# biggity.net
KiCad netlist of a schematic drawn in EAGLE
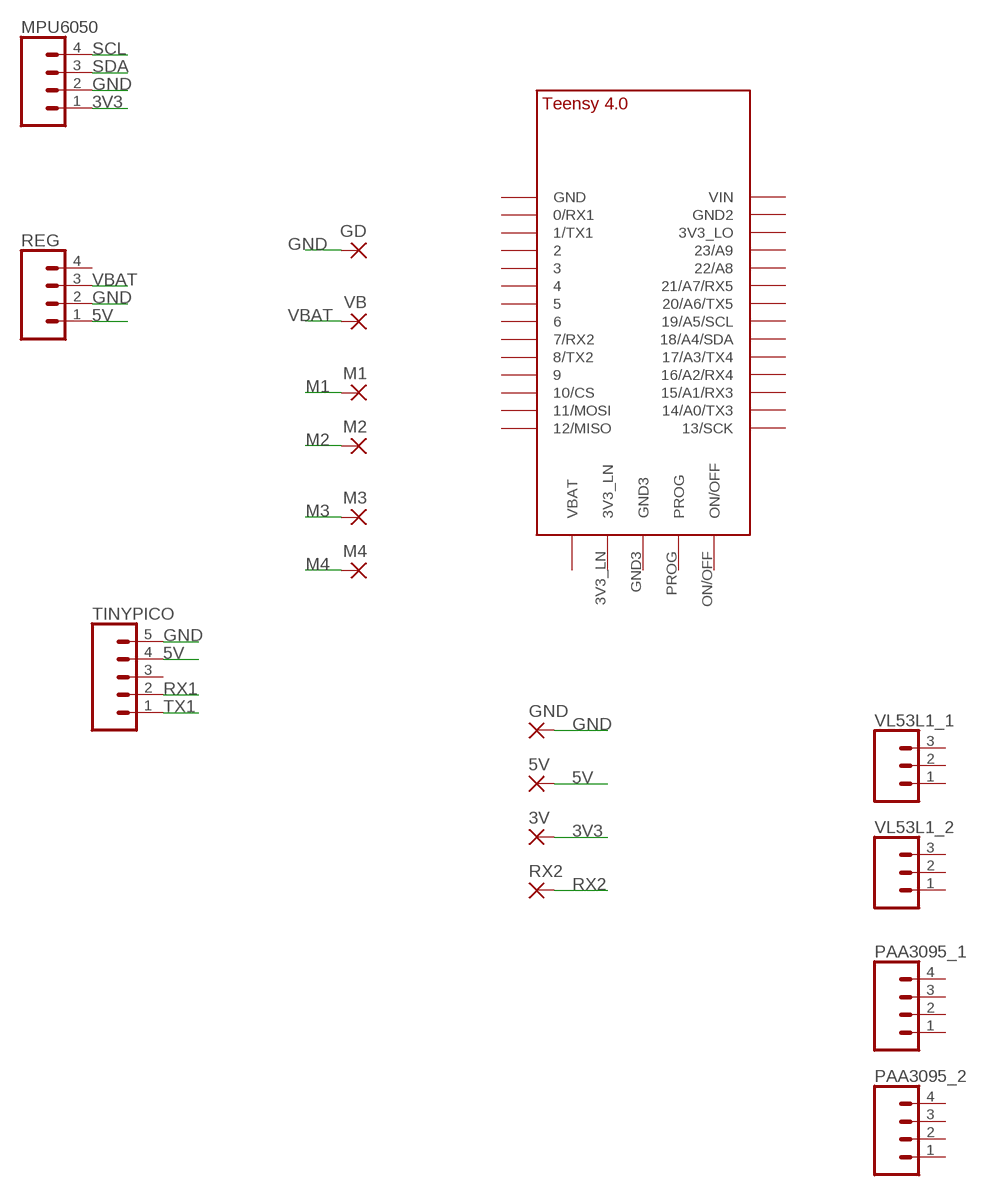
[diagram p0: schematic, sheet 1]

(export (version "E")
  (design (tool "Eeschema 10.0.6"))
  (components
    (comp (ref "3V")
      (value "SMD2")
      (footprint "eagle-import:SMD1,27-2,54")
      (libsource (lib "eagle-import") (part "SMD2"))
    )
    (comp (ref "5V")
      (value "SMD2")
      (footprint "eagle-import:SMD1,27-2,54")
      (libsource (lib "eagle-import") (part "SMD2"))
    )
    (comp (ref "GD")
      (value "SMD2")
      (footprint "eagle-import:SMD1,27-2,54")
      (libsource (lib "eagle-import") (part "SMD2"))
    )
    (comp (ref "GND")
      (value "SMD2")
      (footprint "eagle-import:SMD1,27-2,54")
      (libsource (lib "eagle-import") (part "SMD2"))
    )
    (comp (ref "M1")
      (value "SMD2")
      (footprint "eagle-import:SMD1,27-2,54")
      (libsource (lib "eagle-import") (part "SMD2"))
    )
    (comp (ref "M2")
      (value "SMD2")
      (footprint "eagle-import:SMD1,27-2,54")
      (libsource (lib "eagle-import") (part "SMD2"))
    )
    (comp (ref "M3")
      (value "SMD2")
      (footprint "eagle-import:SMD1,27-2,54")
      (libsource (lib "eagle-import") (part "SMD2"))
    )
    (comp (ref "M4")
      (value "SMD2")
      (footprint "eagle-import:SMD1,27-2,54")
      (libsource (lib "eagle-import") (part "SMD2"))
    )
    (comp (ref "MPU6050")
      (value "CONN_041X04_NO_SILK")
      (footprint "eagle-import:1X04_NO_SILK")
      (libsource (lib "eagle-import") (part "CONN_041X04_NO_SILK"))
    )
    (comp (ref "PAA3095_1")
      (value "CONN_041X04_NO_SILK")
      (footprint "eagle-import:1X04_NO_SILK")
      (libsource (lib "eagle-import") (part "CONN_041X04_NO_SILK"))
    )
    (comp (ref "PAA3095_2")
      (value "CONN_041X04_NO_SILK")
      (footprint "eagle-import:1X04_NO_SILK")
      (libsource (lib "eagle-import") (part "CONN_041X04_NO_SILK"))
    )
    (comp (ref "REG")
      (value "CONN_041X04_NO_SILK")
      (footprint "eagle-import:1X04_NO_SILK")
      (libsource (lib "eagle-import") (part "CONN_041X04_NO_SILK"))
    )
    (comp (ref "RX2")
      (value "SMD2")
      (footprint "eagle-import:SMD1,27-2,54")
      (libsource (lib "eagle-import") (part "SMD2"))
    )
    (comp (ref "TINYPICO")
      (value "CONN_05NO_SILK")
      (footprint "eagle-import:1X05_NO_SILK")
      (libsource (lib "eagle-import") (part "CONN_05NO_SILK"))
    )
    (comp (ref "U$1")
      (value "TEENSY_4.0")
      (footprint "eagle-import:TEENSY_4.0")
      (libsource (lib "eagle-import") (part "TEENSY_4.0"))
    )
    (comp (ref "VB")
      (value "SMD2")
      (footprint "eagle-import:SMD1,27-2,54")
      (libsource (lib "eagle-import") (part "SMD2"))
    )
    (comp (ref "VL53L1_1")
      (value "CONN_031X03_NO_SILK")
      (footprint "eagle-import:1X03_NO_SILK")
      (libsource (lib "eagle-import") (part "CONN_031X03_NO_SILK"))
    )
    (comp (ref "VL53L1_2")
      (value "CONN_031X03_NO_SILK")
      (footprint "eagle-import:1X03_NO_SILK")
      (libsource (lib "eagle-import") (part "CONN_031X03_NO_SILK"))
    )
  )
  (nets
    (net (code "1") (name "/3V3") (class "Default")
      (node (ref "3V") (pin "1") (pinfunction "P_1") (pintype "passive"))
      (node (ref "MPU6050") (pin "1") (pinfunction "1_1") (pintype "passive"))
    )
    (net (code "2") (name "/5V") (class "Default")
      (node (ref "5V") (pin "1") (pinfunction "P_1") (pintype "passive"))
      (node (ref "REG") (pin "1") (pinfunction "1_1") (pintype "passive"))
      (node (ref "TINYPICO") (pin "4") (pinfunction "4_4") (pintype "passive"))
    )
    (net (code "3") (name "/GND") (class "Default")
      (node (ref "GD") (pin "1") (pinfunction "P_1") (pintype "passive"))
      (node (ref "GND") (pin "1") (pinfunction "P_1") (pintype "passive"))
      (node (ref "MPU6050") (pin "2") (pinfunction "2_2") (pintype "passive"))
      (node (ref "REG") (pin "2") (pinfunction "2_2") (pintype "passive"))
      (node (ref "TINYPICO") (pin "5") (pinfunction "5_5") (pintype "passive"))
    )
    (net (code "4") (name "/M1") (class "Default")
      (node (ref "M1") (pin "1") (pinfunction "P_1") (pintype "passive"))
    )
    (net (code "5") (name "/M2") (class "Default")
      (node (ref "M2") (pin "1") (pinfunction "P_1") (pintype "passive"))
    )
    (net (code "6") (name "/M3") (class "Default")
      (node (ref "M3") (pin "1") (pinfunction "P_1") (pintype "passive"))
    )
    (net (code "7") (name "/M4") (class "Default")
      (node (ref "M4") (pin "1") (pinfunction "P_1") (pintype "passive"))
    )
    (net (code "8") (name "/RX1") (class "Default")
      (node (ref "TINYPICO") (pin "2") (pinfunction "2_2") (pintype "passive"))
    )
    (net (code "9") (name "/RX2") (class "Default")
      (node (ref "RX2") (pin "1") (pinfunction "P_1") (pintype "passive"))
    )
    (net (code "10") (name "/SCL") (class "Default")
      (node (ref "MPU6050") (pin "4") (pinfunction "4_4") (pintype "passive"))
    )
    (net (code "11") (name "/SDA") (class "Default")
      (node (ref "MPU6050") (pin "3") (pinfunction "3_3") (pintype "passive"))
    )
    (net (code "12") (name "/TX1") (class "Default")
      (node (ref "TINYPICO") (pin "1") (pinfunction "1_1") (pintype "passive"))
    )
    (net (code "13") (name "/VBAT") (class "Default")
      (node (ref "REG") (pin "3") (pinfunction "3_3") (pintype "passive"))
      (node (ref "VB") (pin "1") (pinfunction "P_1") (pintype "passive"))
    )
    (net (code "14") (name "unconnected-(PAA3095_1-Pad1)") (class "Default")
      (node (ref "PAA3095_1") (pin "1") (pinfunction "1_1") (pintype "passive"))
    )
    (net (code "15") (name "unconnected-(PAA3095_1-Pad2)") (class "Default")
      (node (ref "PAA3095_1") (pin "2") (pinfunction "2_2") (pintype "passive"))
    )
    (net (code "16") (name "unconnected-(PAA3095_1-Pad3)") (class "Default")
      (node (ref "PAA3095_1") (pin "3") (pinfunction "3_3") (pintype "passive"))
    )
    (net (code "17") (name "unconnected-(PAA3095_1-Pad4)") (class "Default")
      (node (ref "PAA3095_1") (pin "4") (pinfunction "4_4") (pintype "passive"))
    )
    (net (code "18") (name "unconnected-(PAA3095_2-Pad1)") (class "Default")
      (node (ref "PAA3095_2") (pin "1") (pinfunction "1_1") (pintype "passive"))
    )
    (net (code "19") (name "unconnected-(PAA3095_2-Pad2)") (class "Default")
      (node (ref "PAA3095_2") (pin "2") (pinfunction "2_2") (pintype "passive"))
    )
    (net (code "20") (name "unconnected-(PAA3095_2-Pad3)") (class "Default")
      (node (ref "PAA3095_2") (pin "3") (pinfunction "3_3") (pintype "passive"))
    )
    (net (code "21") (name "unconnected-(PAA3095_2-Pad4)") (class "Default")
      (node (ref "PAA3095_2") (pin "4") (pinfunction "4_4") (pintype "passive"))
    )
    (net (code "22") (name "unconnected-(REG-Pad4)") (class "Default")
      (node (ref "REG") (pin "4") (pinfunction "4_4") (pintype "passive"))
    )
    (net (code "23") (name "unconnected-(TINYPICO-Pad3)") (class "Default")
      (node (ref "TINYPICO") (pin "3") (pinfunction "3_3") (pintype "passive"))
    )
    (net (code "24") (name "unconnected-(U$1-0{slash}RX1-Pad0{slash}RX)") (class "Default")
      (node (ref "U$1") (pin "0/RX") (pinfunction "0/RX1_0/RX") (pintype "bidirectional"))
    )
    (net (code "25") (name "unconnected-(U$1-1{slash}TX1-Pad1{slash}TX)") (class "Default")
      (node (ref "U$1") (pin "1/TX") (pinfunction "1/TX1_1/TX") (pintype "bidirectional"))
    )
    (net (code "26") (name "unconnected-(U$1-3-Pad3{slash}CANTX)") (class "Default")
      (node (ref "U$1") (pin "3/CANTX") (pinfunction "3_3/CANTX") (pintype "bidirectional"))
    )
    (net (code "27") (name "unconnected-(U$1-4-Pad4{slash}CANRX)") (class "Default")
      (node (ref "U$1") (pin "4/CANRX") (pinfunction "4_4/CANRX") (pintype "bidirectional"))
    )
    (net (code "28") (name "unconnected-(U$1-7{slash}RX2-Pad7)") (class "Default")
      (node (ref "U$1") (pin "7") (pinfunction "7/RX2_7") (pintype "bidirectional"))
    )
    (net (code "29") (name "unconnected-(U$1-8{slash}TX2-Pad8)") (class "Default")
      (node (ref "U$1") (pin "8") (pinfunction "8/TX2_8") (pintype "bidirectional"))
    )
    (net (code "30") (name "unconnected-(U$1-9-Pad9{slash}CS)") (class "Default")
      (node (ref "U$1") (pin "9/CS") (pinfunction "9_9/CS") (pintype "bidirectional"))
    )
    (net (code "31") (name "unconnected-(U$1-14{slash}A0{slash}TX3-Pad14{slash}A0)") (class "Default")
      (node (ref "U$1") (pin "14/A0") (pinfunction "14/A0/TX3_14/A0") (pintype "bidirectional"))
    )
    (net (code "32") (name "unconnected-(U$1-15{slash}A1{slash}RX3-Pad15{slash}A1)") (class "Default")
      (node (ref "U$1") (pin "15/A1") (pinfunction "15/A1/RX3_15/A1") (pintype "bidirectional"))
    )
    (net (code "33") (name "unconnected-(U$1-16{slash}A2{slash}RX4-Pad16{slash}A2)") (class "Default")
      (node (ref "U$1") (pin "16/A2") (pinfunction "16/A2/RX4_16/A2") (pintype "bidirectional"))
    )
    (net (code "34") (name "unconnected-(U$1-17{slash}A3{slash}TX4-Pad17{slash}A3)") (class "Default")
      (node (ref "U$1") (pin "17/A3") (pinfunction "17/A3/TX4_17/A3") (pintype "bidirectional"))
    )
    (net (code "35") (name "unconnected-(U$1-20{slash}A6{slash}TX5-Pad20{slash}A6)") (class "Default")
      (node (ref "U$1") (pin "20/A6") (pinfunction "20/A6/TX5_20/A6") (pintype "bidirectional"))
    )
    (net (code "36") (name "unconnected-(U$1-21{slash}A7{slash}RX5-Pad21{slash}A7)") (class "Default")
      (node (ref "U$1") (pin "21/A7") (pinfunction "21/A7/RX5_21/A7") (pintype "bidirectional"))
    )
    (net (code "37") (name "unconnected-(U$1-Pad2)") (class "Default")
      (node (ref "U$1") (pin "2") (pinfunction "2_2") (pintype "bidirectional"))
    )
    (net (code "38") (name "unconnected-(U$1-Pad3V3_LN)") (class "Default")
      (node (ref "U$1") (pin "3V3_LN") (pinfunction "3V3_LN_3V3_LN") (pintype "bidirectional"))
    )
    (net (code "39") (name "unconnected-(U$1-Pad3V3_LO)") (class "Default")
      (node (ref "U$1") (pin "3V3_LO") (pinfunction "3V3_LO_3V3_LO") (pintype "bidirectional"))
    )
    (net (code "40") (name "unconnected-(U$1-Pad5)") (class "Default")
      (node (ref "U$1") (pin "5") (pinfunction "5_5") (pintype "bidirectional"))
    )
    (net (code "41") (name "unconnected-(U$1-Pad6)") (class "Default")
      (node (ref "U$1") (pin "6") (pinfunction "6_6") (pintype "bidirectional"))
    )
    (net (code "42") (name "unconnected-(U$1-Pad10{slash}CS)") (class "Default")
      (node (ref "U$1") (pin "10/CS") (pinfunction "10/CS_10/CS") (pintype "bidirectional"))
    )
    (net (code "43") (name "unconnected-(U$1-Pad11{slash}MOSI)") (class "Default")
      (node (ref "U$1") (pin "11/MOSI") (pinfunction "11/MOSI_11/MOSI") (pintype "bidirectional"))
    )
    (net (code "44") (name "unconnected-(U$1-Pad12{slash}MISO)") (class "Default")
      (node (ref "U$1") (pin "12/MISO") (pinfunction "12/MISO_12/MISO") (pintype "bidirectional"))
    )
    (net (code "45") (name "unconnected-(U$1-Pad13{slash}SCK)") (class "Default")
      (node (ref "U$1") (pin "13/SCK") (pinfunction "13/SCK_13/SCK") (pintype "bidirectional"))
    )
    (net (code "46") (name "unconnected-(U$1-Pad18{slash}A4{slash}SDA)") (class "Default")
      (node (ref "U$1") (pin "18/A4/SDA") (pinfunction "18/A4/SDA_18/A4/SDA") (pintype "bidirectional"))
    )
    (net (code "47") (name "unconnected-(U$1-Pad19{slash}A5{slash}SCL)") (class "Default")
      (node (ref "U$1") (pin "19/A5/SCL") (pinfunction "19/A5/SCL_19/A5/SCL") (pintype "bidirectional"))
    )
    (net (code "48") (name "unconnected-(U$1-Pad22{slash}A8)") (class "Default")
      (node (ref "U$1") (pin "22/A8") (pinfunction "22/A8_22/A8") (pintype "bidirectional"))
    )
    (net (code "49") (name "unconnected-(U$1-Pad23{slash}A9)") (class "Default")
      (node (ref "U$1") (pin "23/A9") (pinfunction "23/A9_23/A9") (pintype "bidirectional"))
    )
    (net (code "50") (name "unconnected-(U$1-PadGND)") (class "Default")
      (node (ref "U$1") (pin "GND") (pinfunction "GND_GND") (pintype "bidirectional"))
    )
    (net (code "51") (name "unconnected-(U$1-PadGND2)") (class "Default")
      (node (ref "U$1") (pin "GND2") (pinfunction "GND2_GND2") (pintype "bidirectional"))
    )
    (net (code "52") (name "unconnected-(U$1-PadGND3)") (class "Default")
      (node (ref "U$1") (pin "GND3") (pinfunction "GND3_GND3") (pintype "bidirectional"))
    )
    (net (code "53") (name "unconnected-(U$1-PadON{slash}OFF)") (class "Default")
      (node (ref "U$1") (pin "ON/OFF") (pinfunction "ON/OFF_ON/OFF") (pintype "bidirectional"))
    )
    (net (code "54") (name "unconnected-(U$1-PadPROG)") (class "Default")
      (node (ref "U$1") (pin "PROG") (pinfunction "PROG_PROG") (pintype "bidirectional"))
    )
    (net (code "55") (name "unconnected-(U$1-PadVIN)") (class "Default")
      (node (ref "U$1") (pin "VIN") (pinfunction "VIN_VIN") (pintype "bidirectional"))
    )
    (net (code "56") (name "unconnected-(U$1-VBAT-PadVBAT\\)") (class "Default")
      (node (ref "U$1") (pin "VBAT\\") (pinfunction "VBAT_VBAT\\") (pintype "bidirectional"))
    )
    (net (code "57") (name "unconnected-(VL53L1_1-Pad1)") (class "Default")
      (node (ref "VL53L1_1") (pin "1") (pinfunction "1_1") (pintype "passive"))
    )
    (net (code "58") (name "unconnected-(VL53L1_1-Pad2)") (class "Default")
      (node (ref "VL53L1_1") (pin "2") (pinfunction "2_2") (pintype "passive"))
    )
    (net (code "59") (name "unconnected-(VL53L1_1-Pad3)") (class "Default")
      (node (ref "VL53L1_1") (pin "3") (pinfunction "3_3") (pintype "passive"))
    )
    (net (code "60") (name "unconnected-(VL53L1_2-Pad1)") (class "Default")
      (node (ref "VL53L1_2") (pin "1") (pinfunction "1_1") (pintype "passive"))
    )
    (net (code "61") (name "unconnected-(VL53L1_2-Pad2)") (class "Default")
      (node (ref "VL53L1_2") (pin "2") (pinfunction "2_2") (pintype "passive"))
    )
    (net (code "62") (name "unconnected-(VL53L1_2-Pad3)") (class "Default")
      (node (ref "VL53L1_2") (pin "3") (pinfunction "3_3") (pintype "passive"))
    )
  )
)
